# AudioAmplifier.net
KiCad netlist of a schematic drawn in EAGLE
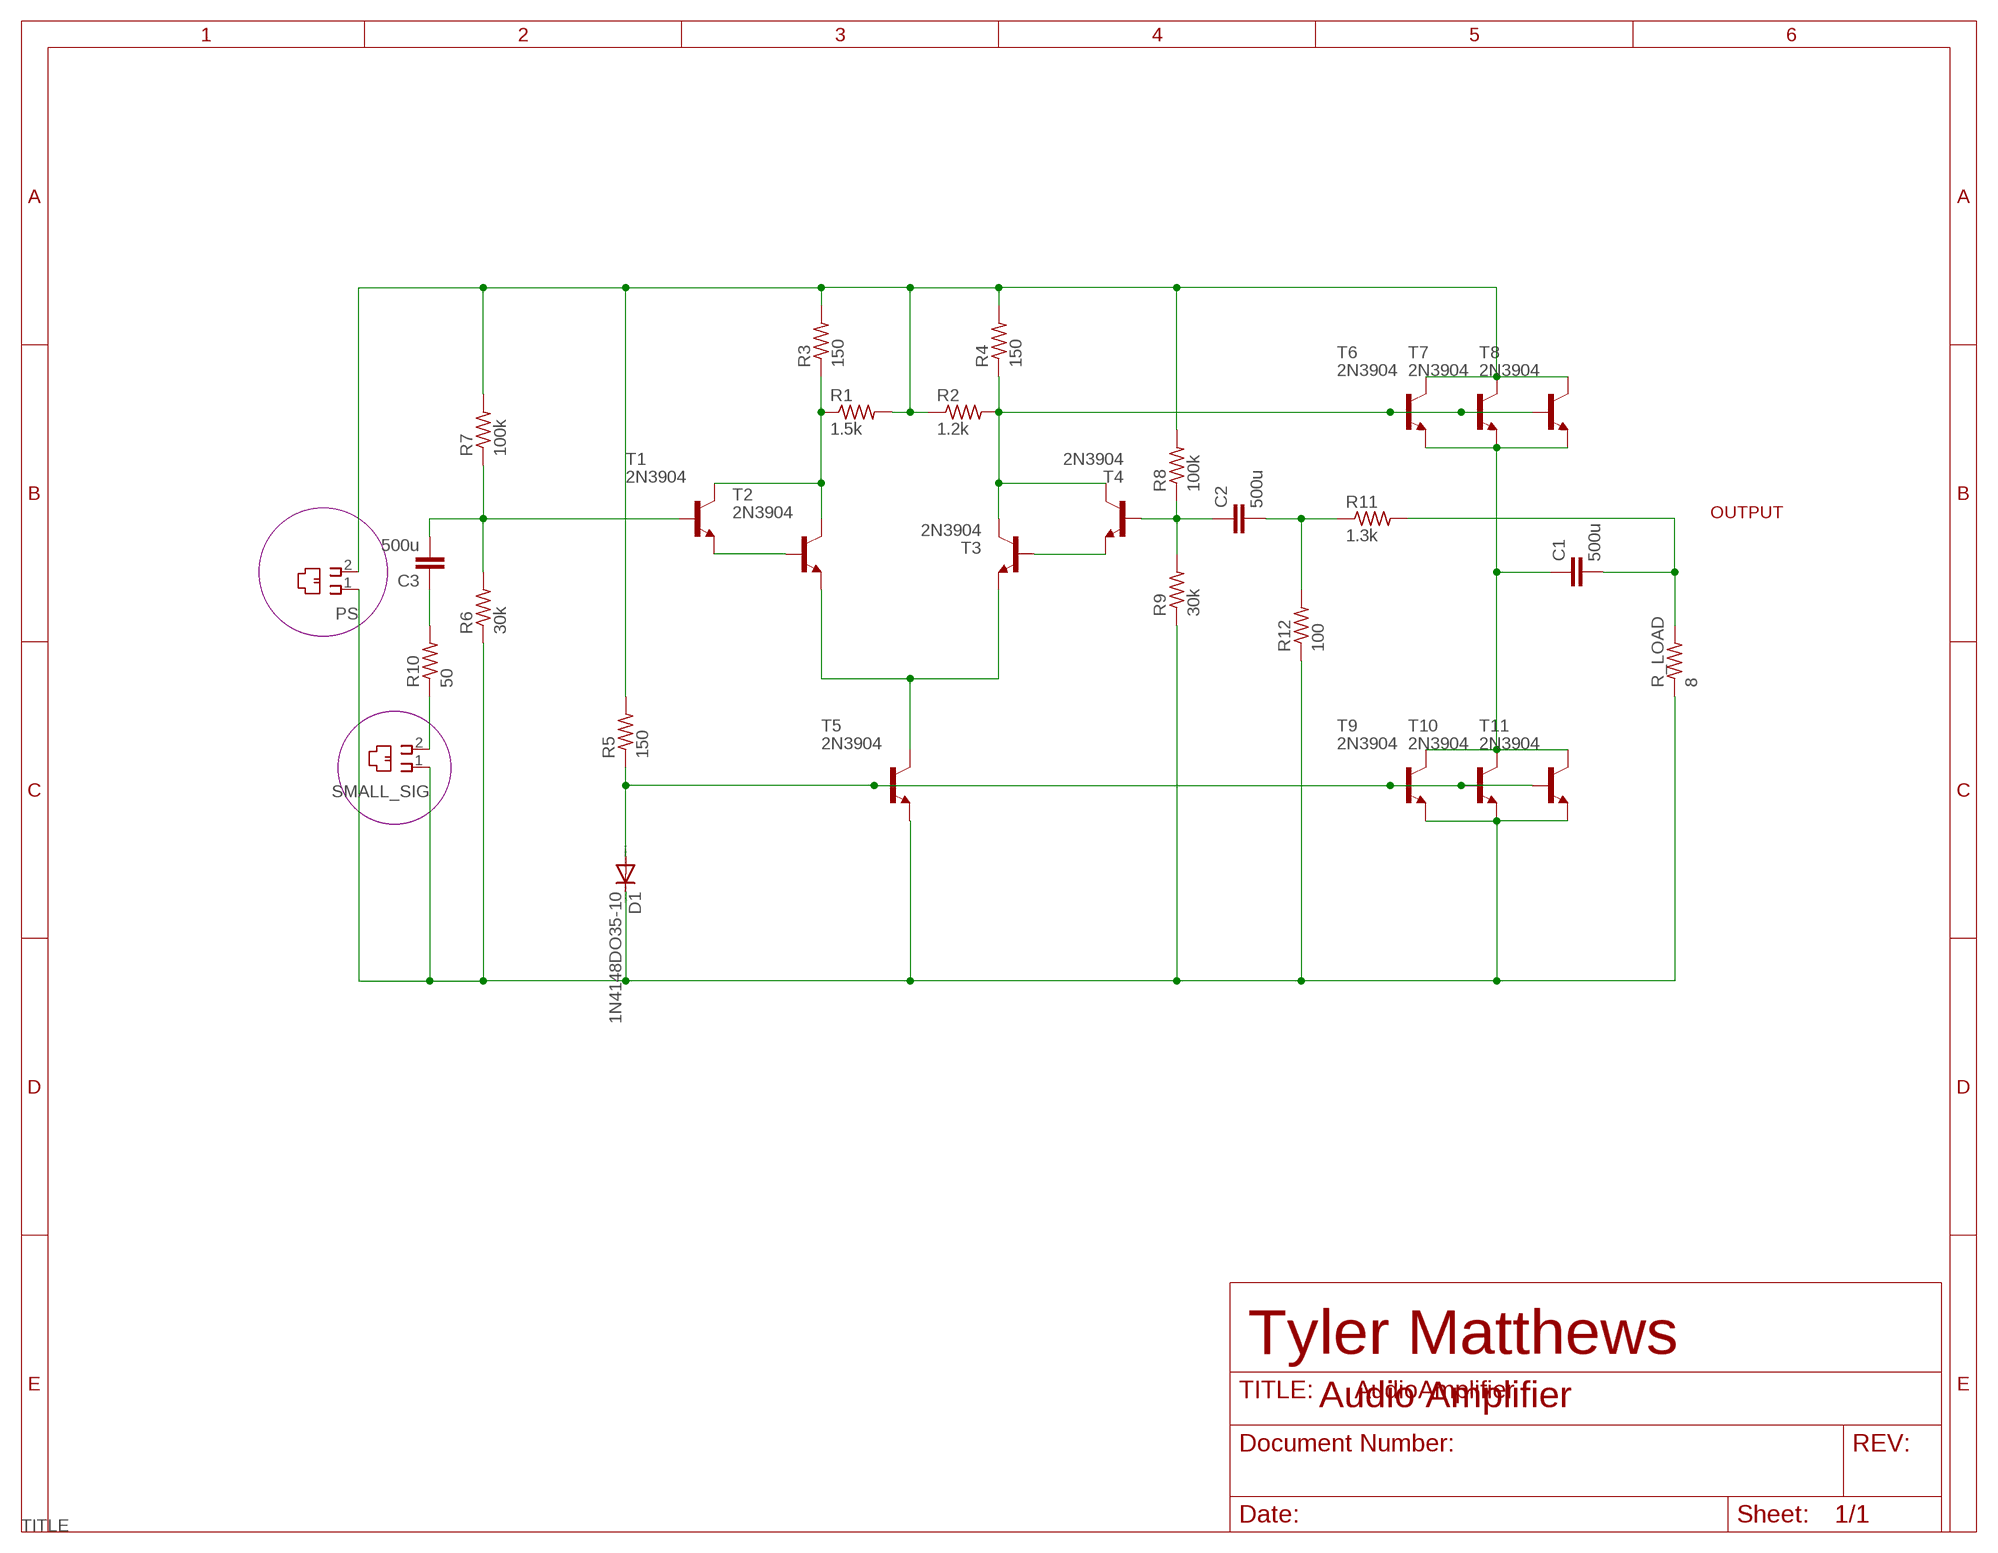
[diagram p0: schematic, sheet 1]

(export (version "E")
  (design (tool "Eeschema 10.0.6"))
  (components
    (comp (ref "C1")
      (value "500u")
      (footprint "eagle-import:C2.5-2")
      (libsource (lib "eagle-import") (part "C2.5/2"))
    )
    (comp (ref "C2")
      (value "500u")
      (footprint "eagle-import:C2.5-2")
      (libsource (lib "eagle-import") (part "C2.5/2"))
    )
    (comp (ref "C3")
      (value "500u")
      (footprint "eagle-import:C2.5-2")
      (libsource (lib "eagle-import") (part "C2.5/2"))
    )
    (comp (ref "D1")
      (value "1N4148DO35-10")
      (footprint "eagle-import:DO35-10")
      (libsource (lib "eagle-import") (part "1N4148DO35-10"))
    )
    (comp (ref "PS")
      (value "215876-7")
      (footprint "eagle-import:215876-7")
      (libsource (lib "eagle-import") (part "215876-7"))
    )
    (comp (ref "R1")
      (value "1.5k")
      (footprint "eagle-import:0204V")
      (libsource (lib "eagle-import") (part "R-US_0204/2V"))
    )
    (comp (ref "R2")
      (value "1.2k")
      (footprint "eagle-import:0204V")
      (libsource (lib "eagle-import") (part "R-US_0204/2V"))
    )
    (comp (ref "R3")
      (value "150")
      (footprint "eagle-import:0204V")
      (libsource (lib "eagle-import") (part "R-US_0204/2V"))
    )
    (comp (ref "R4")
      (value "150")
      (footprint "eagle-import:0204V")
      (libsource (lib "eagle-import") (part "R-US_0204/2V"))
    )
    (comp (ref "R5")
      (value "150")
      (footprint "eagle-import:0204V")
      (libsource (lib "eagle-import") (part "R-US_0204/2V"))
    )
    (comp (ref "R6")
      (value "30k")
      (footprint "eagle-import:0204V")
      (libsource (lib "eagle-import") (part "R-US_0204/2V"))
    )
    (comp (ref "R7")
      (value "100k")
      (footprint "eagle-import:0204V")
      (libsource (lib "eagle-import") (part "R-US_0204/2V"))
    )
    (comp (ref "R8")
      (value "100k")
      (footprint "eagle-import:0204V")
      (libsource (lib "eagle-import") (part "R-US_0204/2V"))
    )
    (comp (ref "R9")
      (value "30k")
      (footprint "eagle-import:0204V")
      (libsource (lib "eagle-import") (part "R-US_0204/2V"))
    )
    (comp (ref "R10")
      (value "50")
      (footprint "eagle-import:0204V")
      (libsource (lib "eagle-import") (part "R-US_0204/2V"))
    )
    (comp (ref "R11")
      (value "1.3k")
      (footprint "eagle-import:0204V")
      (libsource (lib "eagle-import") (part "R-US_0204/2V"))
    )
    (comp (ref "R12")
      (value "100")
      (footprint "eagle-import:0204V")
      (libsource (lib "eagle-import") (part "R-US_0204/2V"))
    )
    (comp (ref "R_LOAD")
      (value "8")
      (footprint "eagle-import:0204V")
      (libsource (lib "eagle-import") (part "R-US_0204/2V"))
    )
    (comp (ref "SMALL_SIG")
      (value "215876-7")
      (footprint "eagle-import:215876-7")
      (libsource (lib "eagle-import") (part "215876-7"))
    )
    (comp (ref "T1")
      (value "2N3904")
      (footprint "eagle-import:TO92")
      (libsource (lib "eagle-import") (part "2N3904"))
    )
    (comp (ref "T2")
      (value "2N3904")
      (footprint "eagle-import:TO92")
      (libsource (lib "eagle-import") (part "2N3904"))
    )
    (comp (ref "T3")
      (value "2N3904")
      (footprint "eagle-import:TO92")
      (libsource (lib "eagle-import") (part "2N3904"))
    )
    (comp (ref "T4")
      (value "2N3904")
      (footprint "eagle-import:TO92")
      (libsource (lib "eagle-import") (part "2N3904"))
    )
    (comp (ref "T5")
      (value "2N3904")
      (footprint "eagle-import:TO92")
      (libsource (lib "eagle-import") (part "2N3904"))
    )
    (comp (ref "T6")
      (value "2N3904")
      (footprint "eagle-import:TO92")
      (libsource (lib "eagle-import") (part "2N3904"))
    )
    (comp (ref "T7")
      (value "2N3904")
      (footprint "eagle-import:TO92")
      (libsource (lib "eagle-import") (part "2N3904"))
    )
    (comp (ref "T8")
      (value "2N3904")
      (footprint "eagle-import:TO92")
      (libsource (lib "eagle-import") (part "2N3904"))
    )
    (comp (ref "T9")
      (value "2N3904")
      (footprint "eagle-import:TO92")
      (libsource (lib "eagle-import") (part "2N3904"))
    )
    (comp (ref "T10")
      (value "2N3904")
      (footprint "eagle-import:TO92")
      (libsource (lib "eagle-import") (part "2N3904"))
    )
    (comp (ref "T11")
      (value "2N3904")
      (footprint "eagle-import:TO92")
      (libsource (lib "eagle-import") (part "2N3904"))
    )
  )
  (nets
    (net (code "1") (name "/OUTPUT") (class "Default")
      (node (ref "C1") (pin "2") (pinfunction "2_2") (pintype "passive"))
      (node (ref "R11") (pin "2") (pinfunction "2_2") (pintype "passive"))
      (node (ref "R_LOAD") (pin "2") (pinfunction "2_2") (pintype "passive"))
    )
    (net (code "2") (name "Net-(C2-Pad2)") (class "Default")
      (node (ref "C2") (pin "2") (pinfunction "2_2") (pintype "passive"))
      (node (ref "R11") (pin "1") (pinfunction "1_1") (pintype "passive"))
      (node (ref "R12") (pin "2") (pinfunction "2_2") (pintype "passive"))
    )
    (net (code "3") (name "Net-(C3-Pad1)") (class "Default")
      (node (ref "C3") (pin "1") (pinfunction "1_1") (pintype "passive"))
      (node (ref "R10") (pin "2") (pinfunction "2_2") (pintype "passive"))
    )
    (net (code "4") (name "Net-(R10-Pad1)") (class "Default")
      (node (ref "R10") (pin "1") (pinfunction "1_1") (pintype "passive"))
      (node (ref "SMALL_SIG") (pin "2") (pinfunction "2_2") (pintype "passive"))
    )
    (net (code "5") (name "Net-(T1-B)") (class "Default")
      (node (ref "C3") (pin "2") (pinfunction "2_2") (pintype "passive"))
      (node (ref "R6") (pin "2") (pinfunction "2_2") (pintype "passive"))
      (node (ref "R7") (pin "1") (pinfunction "1_1") (pintype "passive"))
      (node (ref "T1") (pin "2") (pinfunction "B_2") (pintype "passive"))
    )
    (net (code "6") (name "Net-(T1-C)") (class "Default")
      (node (ref "R1") (pin "1") (pinfunction "1_1") (pintype "passive"))
      (node (ref "R3") (pin "1") (pinfunction "1_1") (pintype "passive"))
      (node (ref "T1") (pin "1") (pinfunction "C_1") (pintype "passive"))
      (node (ref "T2") (pin "1") (pinfunction "C_1") (pintype "passive"))
    )
    (net (code "7") (name "Net-(T1-E)") (class "Default")
      (node (ref "T1") (pin "3") (pinfunction "E_3") (pintype "passive"))
      (node (ref "T2") (pin "2") (pinfunction "B_2") (pintype "passive"))
    )
    (net (code "8") (name "Net-(T2-E)") (class "Default")
      (node (ref "T2") (pin "3") (pinfunction "E_3") (pintype "passive"))
      (node (ref "T3") (pin "3") (pinfunction "E_3") (pintype "passive"))
      (node (ref "T5") (pin "1") (pinfunction "C_1") (pintype "passive"))
    )
    (net (code "9") (name "Net-(T3-B)") (class "Default")
      (node (ref "T3") (pin "2") (pinfunction "B_2") (pintype "passive"))
      (node (ref "T4") (pin "3") (pinfunction "E_3") (pintype "passive"))
    )
    (net (code "10") (name "Net-(T3-C)") (class "Default")
      (node (ref "R2") (pin "2") (pinfunction "2_2") (pintype "passive"))
      (node (ref "R4") (pin "1") (pinfunction "1_1") (pintype "passive"))
      (node (ref "T3") (pin "1") (pinfunction "C_1") (pintype "passive"))
      (node (ref "T4") (pin "1") (pinfunction "C_1") (pintype "passive"))
      (node (ref "T6") (pin "2") (pinfunction "B_2") (pintype "passive"))
      (node (ref "T7") (pin "2") (pinfunction "B_2") (pintype "passive"))
      (node (ref "T8") (pin "2") (pinfunction "B_2") (pintype "passive"))
    )
    (net (code "11") (name "Net-(T4-B)") (class "Default")
      (node (ref "C2") (pin "1") (pinfunction "1_1") (pintype "passive"))
      (node (ref "R8") (pin "1") (pinfunction "1_1") (pintype "passive"))
      (node (ref "R9") (pin "2") (pinfunction "2_2") (pintype "passive"))
      (node (ref "T4") (pin "2") (pinfunction "B_2") (pintype "passive"))
    )
    (net (code "12") (name "Net-(T6-C)") (class "Default")
      (node (ref "PS") (pin "2") (pinfunction "2_2") (pintype "passive"))
      (node (ref "R1") (pin "2") (pinfunction "2_2") (pintype "passive"))
      (node (ref "R2") (pin "1") (pinfunction "1_1") (pintype "passive"))
      (node (ref "R3") (pin "2") (pinfunction "2_2") (pintype "passive"))
      (node (ref "R4") (pin "2") (pinfunction "2_2") (pintype "passive"))
      (node (ref "R5") (pin "2") (pinfunction "2_2") (pintype "passive"))
      (node (ref "R7") (pin "2") (pinfunction "2_2") (pintype "passive"))
      (node (ref "R8") (pin "2") (pinfunction "2_2") (pintype "passive"))
      (node (ref "T6") (pin "1") (pinfunction "C_1") (pintype "passive"))
      (node (ref "T7") (pin "1") (pinfunction "C_1") (pintype "passive"))
      (node (ref "T8") (pin "1") (pinfunction "C_1") (pintype "passive"))
    )
    (net (code "13") (name "Net-(T10-B)") (class "Default")
      (node (ref "D1") (pin "A") (pinfunction "A_A") (pintype "passive"))
      (node (ref "R5") (pin "1") (pinfunction "1_1") (pintype "passive"))
      (node (ref "T10") (pin "2") (pinfunction "B_2") (pintype "passive"))
      (node (ref "T11") (pin "2") (pinfunction "B_2") (pintype "passive"))
      (node (ref "T5") (pin "2") (pinfunction "B_2") (pintype "passive"))
      (node (ref "T9") (pin "2") (pinfunction "B_2") (pintype "passive"))
    )
    (net (code "14") (name "Net-(T10-C)") (class "Default")
      (node (ref "C1") (pin "1") (pinfunction "1_1") (pintype "passive"))
      (node (ref "T10") (pin "1") (pinfunction "C_1") (pintype "passive"))
      (node (ref "T11") (pin "1") (pinfunction "C_1") (pintype "passive"))
      (node (ref "T6") (pin "3") (pinfunction "E_3") (pintype "passive"))
      (node (ref "T7") (pin "3") (pinfunction "E_3") (pintype "passive"))
      (node (ref "T8") (pin "3") (pinfunction "E_3") (pintype "passive"))
      (node (ref "T9") (pin "1") (pinfunction "C_1") (pintype "passive"))
    )
    (net (code "15") (name "Net-(T10-E)") (class "Default")
      (node (ref "D1") (pin "C") (pinfunction "C_C") (pintype "passive"))
      (node (ref "PS") (pin "1") (pinfunction "1_1") (pintype "passive"))
      (node (ref "R12") (pin "1") (pinfunction "1_1") (pintype "passive"))
      (node (ref "R6") (pin "1") (pinfunction "1_1") (pintype "passive"))
      (node (ref "R9") (pin "1") (pinfunction "1_1") (pintype "passive"))
      (node (ref "R_LOAD") (pin "1") (pinfunction "1_1") (pintype "passive"))
      (node (ref "SMALL_SIG") (pin "1") (pinfunction "1_1") (pintype "passive"))
      (node (ref "T10") (pin "3") (pinfunction "E_3") (pintype "passive"))
      (node (ref "T11") (pin "3") (pinfunction "E_3") (pintype "passive"))
      (node (ref "T5") (pin "3") (pinfunction "E_3") (pintype "passive"))
      (node (ref "T9") (pin "3") (pinfunction "E_3") (pintype "passive"))
    )
  )
)
